# XPDR_Board_2.net
KiCad netlist of a schematic drawn in EAGLE
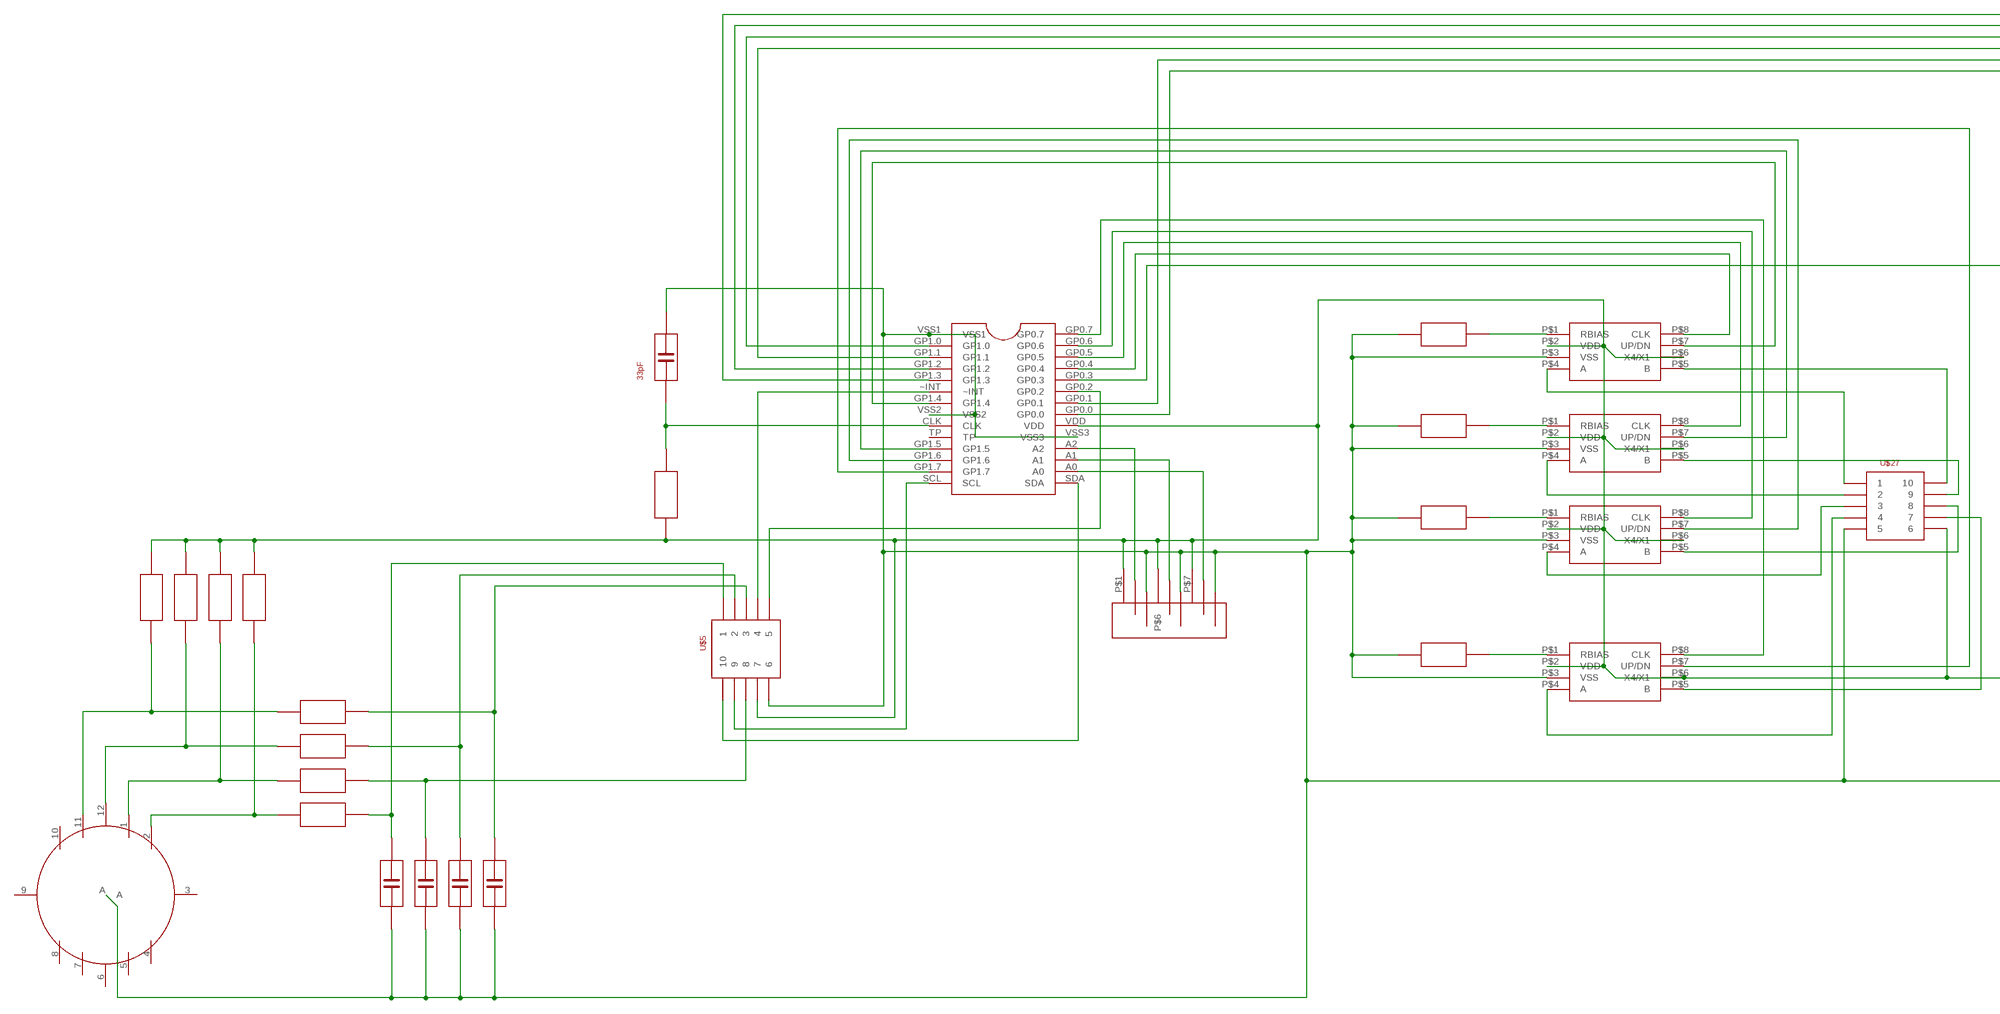
[diagram p0: schematic, sheet 1, part 1 of 2]
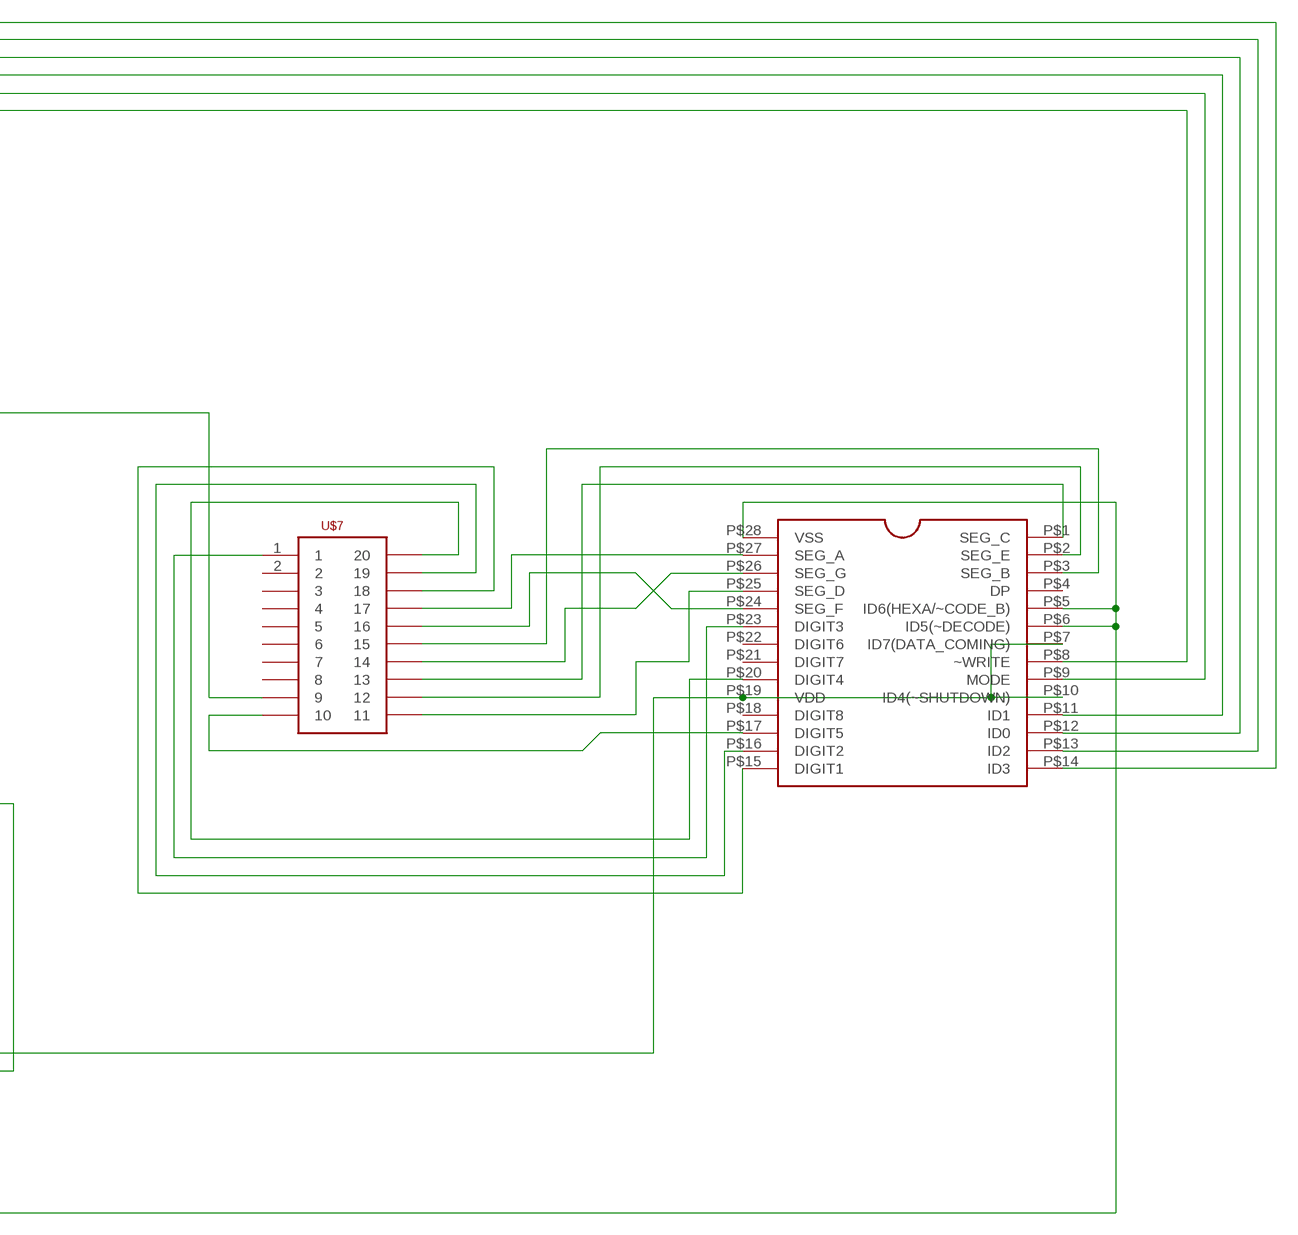
[diagram p1: schematic, sheet 1, part 2 of 2]

(export (version "E")
  (design (tool "Eeschema 10.0.6"))
  (components
    (comp (ref "U$1")
      (value "LS7084")
      (footprint "eagle-import:LS7084")
      (libsource (lib "eagle-import") (part "LS7084"))
    )
    (comp (ref "U$2")
      (value "LS7084")
      (footprint "eagle-import:LS7084")
      (libsource (lib "eagle-import") (part "LS7084"))
    )
    (comp (ref "U$3")
      (value "LS7084")
      (footprint "eagle-import:LS7084")
      (libsource (lib "eagle-import") (part "LS7084"))
    )
    (comp (ref "U$4")
      (value "LS7084")
      (footprint "eagle-import:LS7084")
      (libsource (lib "eagle-import") (part "LS7084"))
    )
    (comp (ref "U$5")
      (value "LISTA_2X5")
      (footprint "eagle-import:LISTA_2X5")
      (libsource (lib "eagle-import") (part "LISTA_2X5"))
    )
    (comp (ref "U$6")
      (value "ICM7228A")
      (footprint "eagle-import:ICM7228A")
      (libsource (lib "eagle-import") (part "ICM7228A"))
    )
    (comp (ref "U$7")
      (value "LISTA_2X10")
      (footprint "eagle-import:LISTA_2X10")
      (libsource (lib "eagle-import") (part "LISTA_2X10"))
    )
    (comp (ref "U$8")
      (value "470M")
      (footprint "eagle-import:REZISTOR")
      (libsource (lib "eagle-import") (part "REZISTOR"))
    )
    (comp (ref "U$9")
      (value "MCP23016")
      (footprint "eagle-import:MCP23016")
      (libsource (lib "eagle-import") (part "MCP23016"))
    )
    (comp (ref "U$10")
      (value "470M")
      (footprint "eagle-import:REZISTOR")
      (libsource (lib "eagle-import") (part "REZISTOR"))
    )
    (comp (ref "U$11")
      (value "ADRESA_0..2")
      (footprint "eagle-import:ADRESA_0..2")
      (libsource (lib "eagle-import") (part "ADRESA_0..2"))
    )
    (comp (ref "U$12")
      (value "470M")
      (footprint "eagle-import:REZISTOR")
      (libsource (lib "eagle-import") (part "REZISTOR"))
    )
    (comp (ref "U$13")
      (value "470M")
      (footprint "eagle-import:REZISTOR")
      (libsource (lib "eagle-import") (part "REZISTOR"))
    )
    (comp (ref "U$14")
      (value "3.9k")
      (footprint "eagle-import:REZISTOR")
      (libsource (lib "eagle-import") (part "REZISTOR"))
    )
    (comp (ref "U$15")
      (value "33pF")
      (footprint "eagle-import:KONDENZATOR")
      (libsource (lib "eagle-import") (part "KONDENZATOR"))
    )
    (comp (ref "U$16")
      (value "ROTARY_SWITCH")
      (footprint "eagle-import:ROTARY_SWITCH")
      (libsource (lib "eagle-import") (part "ROTARY_SWITCH"))
    )
    (comp (ref "U$17")
      (value "REZISTOR")
      (footprint "eagle-import:REZISTOR")
      (libsource (lib "eagle-import") (part "REZISTOR"))
    )
    (comp (ref "U$18")
      (value "REZISTOR")
      (footprint "eagle-import:REZISTOR")
      (libsource (lib "eagle-import") (part "REZISTOR"))
    )
    (comp (ref "U$19")
      (value "REZISTOR")
      (footprint "eagle-import:REZISTOR")
      (libsource (lib "eagle-import") (part "REZISTOR"))
    )
    (comp (ref "U$20")
      (value "REZISTOR")
      (footprint "eagle-import:REZISTOR")
      (libsource (lib "eagle-import") (part "REZISTOR"))
    )
    (comp (ref "U$21")
      (value "REZISTOR")
      (footprint "eagle-import:REZISTOR")
      (libsource (lib "eagle-import") (part "REZISTOR"))
    )
    (comp (ref "U$22")
      (value "REZISTOR")
      (footprint "eagle-import:REZISTOR")
      (libsource (lib "eagle-import") (part "REZISTOR"))
    )
    (comp (ref "U$23")
      (value "REZISTOR")
      (footprint "eagle-import:REZISTOR")
      (libsource (lib "eagle-import") (part "REZISTOR"))
    )
    (comp (ref "U$24")
      (value "REZISTOR")
      (footprint "eagle-import:REZISTOR")
      (libsource (lib "eagle-import") (part "REZISTOR"))
    )
    (comp (ref "U$25")
      (value "KONDENZATOR")
      (footprint "eagle-import:KONDENZATOR")
      (libsource (lib "eagle-import") (part "KONDENZATOR"))
    )
    (comp (ref "U$26")
      (value "KONDENZATOR")
      (footprint "eagle-import:KONDENZATOR")
      (libsource (lib "eagle-import") (part "KONDENZATOR"))
    )
    (comp (ref "U$27")
      (value "LISTA_2X5")
      (footprint "eagle-import:LISTA_2X5")
      (libsource (lib "eagle-import") (part "LISTA_2X5"))
    )
    (comp (ref "U$28")
      (value "KONDENZATOR")
      (footprint "eagle-import:KONDENZATOR")
      (libsource (lib "eagle-import") (part "KONDENZATOR"))
    )
    (comp (ref "U$29")
      (value "KONDENZATOR")
      (footprint "eagle-import:KONDENZATOR")
      (libsource (lib "eagle-import") (part "KONDENZATOR"))
    )
  )
  (nets
    (net (code "1") (name "Net-(U$1-A)") (class "Default")
      (node (ref "U$1") (pin "P$4") (pinfunction "A_P$4") (pintype "bidirectional"))
      (node (ref "U$27") (pin "1") (pinfunction "1_1") (pintype "bidirectional"))
    )
    (net (code "2") (name "Net-(U$1-B)") (class "Default")
      (node (ref "U$1") (pin "P$5") (pinfunction "B_P$5") (pintype "bidirectional"))
      (node (ref "U$27") (pin "10") (pinfunction "10_10") (pintype "bidirectional"))
    )
    (net (code "3") (name "Net-(U$1-CLK)") (class "Default")
      (node (ref "U$1") (pin "P$8") (pinfunction "CLK_P$8") (pintype "bidirectional"))
      (node (ref "U$9") (pin "GP0.4") (pinfunction "GP0.4_GP0.4") (pintype "bidirectional"))
    )
    (net (code "4") (name "Net-(U$1-RBIAS)") (class "Default")
      (node (ref "U$1") (pin "P$1") (pinfunction "RBIAS_P$1") (pintype "bidirectional"))
      (node (ref "U$8") (pin "P$2") (pinfunction "P$2_P$2") (pintype "bidirectional"))
    )
    (net (code "5") (name "Net-(U$1-UP{slash}DN)") (class "Default")
      (node (ref "U$1") (pin "P$7") (pinfunction "UP/DN_P$7") (pintype "bidirectional"))
      (node (ref "U$9") (pin "GP1.4") (pinfunction "GP1.4_GP1.4") (pintype "bidirectional"))
    )
    (net (code "6") (name "Net-(U$1-VDD)") (class "Default")
      (node (ref "U$1") (pin "P$2") (pinfunction "VDD_P$2") (pintype "bidirectional"))
      (node (ref "U$1") (pin "P$6") (pinfunction "X4/X1_P$6") (pintype "bidirectional"))
      (node (ref "U$11") (pin "P$1") (pinfunction "P$1_P$1") (pintype "bidirectional"))
      (node (ref "U$11") (pin "P$6") (pinfunction "P$6_P$6") (pintype "bidirectional"))
      (node (ref "U$11") (pin "P$7") (pinfunction "P$7_P$7") (pintype "bidirectional"))
      (node (ref "U$14") (pin "P$1") (pinfunction "P$1_P$1") (pintype "bidirectional"))
      (node (ref "U$17") (pin "P$1") (pinfunction "P$1_P$1") (pintype "bidirectional"))
      (node (ref "U$18") (pin "P$1") (pinfunction "P$1_P$1") (pintype "bidirectional"))
      (node (ref "U$19") (pin "P$1") (pinfunction "P$1_P$1") (pintype "bidirectional"))
      (node (ref "U$2") (pin "P$2") (pinfunction "VDD_P$2") (pintype "bidirectional"))
      (node (ref "U$2") (pin "P$6") (pinfunction "X4/X1_P$6") (pintype "bidirectional"))
      (node (ref "U$20") (pin "P$1") (pinfunction "P$1_P$1") (pintype "bidirectional"))
      (node (ref "U$27") (pin "6") (pinfunction "6_6") (pintype "bidirectional"))
      (node (ref "U$3") (pin "P$2") (pinfunction "VDD_P$2") (pintype "bidirectional"))
      (node (ref "U$3") (pin "P$6") (pinfunction "X4/X1_P$6") (pintype "bidirectional"))
      (node (ref "U$4") (pin "P$2") (pinfunction "VDD_P$2") (pintype "bidirectional"))
      (node (ref "U$4") (pin "P$6") (pinfunction "X4/X1_P$6") (pintype "bidirectional"))
      (node (ref "U$5") (pin "7") (pinfunction "7_7") (pintype "bidirectional"))
      (node (ref "U$6") (pin "P$10") (pinfunction "ID4(~{SHUTDOWN})_P$10") (pintype "bidirectional"))
      (node (ref "U$6") (pin "P$19") (pinfunction "VDD_P$19") (pintype "bidirectional"))
      (node (ref "U$6") (pin "P$7") (pinfunction "ID7(DATA_COMING)_P$7") (pintype "bidirectional"))
      (node (ref "U$9") (pin "VDD") (pinfunction "VDD_VDD") (pintype "bidirectional"))
    )
    (net (code "7") (name "Net-(U$1-VSS)") (class "Default")
      (node (ref "U$1") (pin "P$3") (pinfunction "VSS_P$3") (pintype "bidirectional"))
      (node (ref "U$10") (pin "P$1") (pinfunction "P$1_P$1") (pintype "bidirectional"))
      (node (ref "U$11") (pin "P$3") (pinfunction "P$3_P$3") (pintype "bidirectional"))
      (node (ref "U$11") (pin "P$4") (pinfunction "P$4_P$4") (pintype "bidirectional"))
      (node (ref "U$11") (pin "P$9") (pinfunction "P$9_P$9") (pintype "bidirectional"))
      (node (ref "U$12") (pin "P$1") (pinfunction "P$1_P$1") (pintype "bidirectional"))
      (node (ref "U$13") (pin "P$1") (pinfunction "P$1_P$1") (pintype "bidirectional"))
      (node (ref "U$15") (pin "P$2") (pinfunction "P$2_P$2") (pintype "bidirectional"))
      (node (ref "U$16") (pin "A") (pinfunction "A_A") (pintype "bidirectional"))
      (node (ref "U$2") (pin "P$3") (pinfunction "VSS_P$3") (pintype "bidirectional"))
      (node (ref "U$25") (pin "P$1") (pinfunction "P$1_P$1") (pintype "bidirectional"))
      (node (ref "U$26") (pin "P$1") (pinfunction "P$1_P$1") (pintype "bidirectional"))
      (node (ref "U$27") (pin "5") (pinfunction "5_5") (pintype "bidirectional"))
      (node (ref "U$28") (pin "P$1") (pinfunction "P$1_P$1") (pintype "bidirectional"))
      (node (ref "U$29") (pin "P$1") (pinfunction "P$1_P$1") (pintype "bidirectional"))
      (node (ref "U$3") (pin "P$3") (pinfunction "VSS_P$3") (pintype "bidirectional"))
      (node (ref "U$4") (pin "P$3") (pinfunction "VSS_P$3") (pintype "bidirectional"))
      (node (ref "U$5") (pin "6") (pinfunction "6_6") (pintype "bidirectional"))
      (node (ref "U$6") (pin "P$28") (pinfunction "VSS_P$28") (pintype "bidirectional"))
      (node (ref "U$6") (pin "P$5") (pinfunction "ID6(HEXA/~{CODE_B})_P$5") (pintype "bidirectional"))
      (node (ref "U$6") (pin "P$6") (pinfunction "ID5(~{DECODE})_P$6") (pintype "bidirectional"))
      (node (ref "U$8") (pin "P$1") (pinfunction "P$1_P$1") (pintype "bidirectional"))
      (node (ref "U$9") (pin "VSS1") (pinfunction "VSS1_VSS1") (pintype "bidirectional"))
      (node (ref "U$9") (pin "VSS2") (pinfunction "VSS2_VSS2") (pintype "bidirectional"))
      (node (ref "U$9") (pin "VSS3") (pinfunction "VSS3_VSS3") (pintype "bidirectional"))
    )
    (net (code "8") (name "Net-(U$2-A)") (class "Default")
      (node (ref "U$2") (pin "P$4") (pinfunction "A_P$4") (pintype "bidirectional"))
      (node (ref "U$27") (pin "2") (pinfunction "2_2") (pintype "bidirectional"))
    )
    (net (code "9") (name "Net-(U$2-B)") (class "Default")
      (node (ref "U$2") (pin "P$5") (pinfunction "B_P$5") (pintype "bidirectional"))
      (node (ref "U$27") (pin "9") (pinfunction "9_9") (pintype "bidirectional"))
    )
    (net (code "10") (name "Net-(U$2-CLK)") (class "Default")
      (node (ref "U$2") (pin "P$8") (pinfunction "CLK_P$8") (pintype "bidirectional"))
      (node (ref "U$9") (pin "GP0.5") (pinfunction "GP0.5_GP0.5") (pintype "bidirectional"))
    )
    (net (code "11") (name "Net-(U$2-RBIAS)") (class "Default")
      (node (ref "U$10") (pin "P$2") (pinfunction "P$2_P$2") (pintype "bidirectional"))
      (node (ref "U$2") (pin "P$1") (pinfunction "RBIAS_P$1") (pintype "bidirectional"))
    )
    (net (code "12") (name "Net-(U$2-UP{slash}DN)") (class "Default")
      (node (ref "U$2") (pin "P$7") (pinfunction "UP/DN_P$7") (pintype "bidirectional"))
      (node (ref "U$9") (pin "GP1.5") (pinfunction "GP1.5_GP1.5") (pintype "bidirectional"))
    )
    (net (code "13") (name "Net-(U$3-A)") (class "Default")
      (node (ref "U$27") (pin "3") (pinfunction "3_3") (pintype "bidirectional"))
      (node (ref "U$3") (pin "P$4") (pinfunction "A_P$4") (pintype "bidirectional"))
    )
    (net (code "14") (name "Net-(U$3-B)") (class "Default")
      (node (ref "U$27") (pin "8") (pinfunction "8_8") (pintype "bidirectional"))
      (node (ref "U$3") (pin "P$5") (pinfunction "B_P$5") (pintype "bidirectional"))
    )
    (net (code "15") (name "Net-(U$3-CLK)") (class "Default")
      (node (ref "U$3") (pin "P$8") (pinfunction "CLK_P$8") (pintype "bidirectional"))
      (node (ref "U$9") (pin "GP0.6") (pinfunction "GP0.6_GP0.6") (pintype "bidirectional"))
    )
    (net (code "16") (name "Net-(U$3-RBIAS)") (class "Default")
      (node (ref "U$12") (pin "P$2") (pinfunction "P$2_P$2") (pintype "bidirectional"))
      (node (ref "U$3") (pin "P$1") (pinfunction "RBIAS_P$1") (pintype "bidirectional"))
    )
    (net (code "17") (name "Net-(U$3-UP{slash}DN)") (class "Default")
      (node (ref "U$3") (pin "P$7") (pinfunction "UP/DN_P$7") (pintype "bidirectional"))
      (node (ref "U$9") (pin "GP1.6") (pinfunction "GP1.6_GP1.6") (pintype "bidirectional"))
    )
    (net (code "18") (name "Net-(U$4-A)") (class "Default")
      (node (ref "U$27") (pin "4") (pinfunction "4_4") (pintype "bidirectional"))
      (node (ref "U$4") (pin "P$4") (pinfunction "A_P$4") (pintype "bidirectional"))
    )
    (net (code "19") (name "Net-(U$4-B)") (class "Default")
      (node (ref "U$27") (pin "7") (pinfunction "7_7") (pintype "bidirectional"))
      (node (ref "U$4") (pin "P$5") (pinfunction "B_P$5") (pintype "bidirectional"))
    )
    (net (code "20") (name "Net-(U$4-CLK)") (class "Default")
      (node (ref "U$4") (pin "P$8") (pinfunction "CLK_P$8") (pintype "bidirectional"))
      (node (ref "U$9") (pin "GP0.7") (pinfunction "GP0.7_GP0.7") (pintype "bidirectional"))
    )
    (net (code "21") (name "Net-(U$4-RBIAS)") (class "Default")
      (node (ref "U$13") (pin "P$2") (pinfunction "P$2_P$2") (pintype "bidirectional"))
      (node (ref "U$4") (pin "P$1") (pinfunction "RBIAS_P$1") (pintype "bidirectional"))
    )
    (net (code "22") (name "Net-(U$4-UP{slash}DN)") (class "Default")
      (node (ref "U$4") (pin "P$7") (pinfunction "UP/DN_P$7") (pintype "bidirectional"))
      (node (ref "U$9") (pin "GP1.7") (pinfunction "GP1.7_GP1.7") (pintype "bidirectional"))
    )
    (net (code "23") (name "Net-(U$5-Pad5)") (class "Default")
      (node (ref "U$5") (pin "5") (pinfunction "5_5") (pintype "bidirectional"))
      (node (ref "U$9") (pin "GP0.2") (pinfunction "GP0.2_GP0.2") (pintype "bidirectional"))
    )
    (net (code "24") (name "Net-(U$5-Pad9)") (class "Default")
      (node (ref "U$5") (pin "9") (pinfunction "9_9") (pintype "bidirectional"))
      (node (ref "U$9") (pin "SCL") (pinfunction "SCL_SCL") (pintype "bidirectional"))
    )
    (net (code "25") (name "Net-(U$5-Pad10)") (class "Default")
      (node (ref "U$5") (pin "10") (pinfunction "10_10") (pintype "bidirectional"))
      (node (ref "U$9") (pin "SDA") (pinfunction "SDA_SDA") (pintype "bidirectional"))
    )
    (net (code "26") (name "Net-(U$6-DIGIT1)") (class "Default")
      (node (ref "U$6") (pin "P$15") (pinfunction "DIGIT1_P$15") (pintype "bidirectional"))
      (node (ref "U$7") (pin "18") (pinfunction "18_18") (pintype "bidirectional"))
    )
    (net (code "27") (name "Net-(U$6-DIGIT2)") (class "Default")
      (node (ref "U$6") (pin "P$16") (pinfunction "DIGIT2_P$16") (pintype "bidirectional"))
      (node (ref "U$7") (pin "19") (pinfunction "19_19") (pintype "bidirectional"))
    )
    (net (code "28") (name "Net-(U$6-DIGIT3)") (class "Default")
      (node (ref "U$6") (pin "P$23") (pinfunction "DIGIT3_P$23") (pintype "bidirectional"))
      (node (ref "U$7") (pin "1") (pinfunction "1_1") (pintype "bidirectional"))
    )
    (net (code "29") (name "Net-(U$6-DIGIT4)") (class "Default")
      (node (ref "U$6") (pin "P$20") (pinfunction "DIGIT4_P$20") (pintype "bidirectional"))
      (node (ref "U$7") (pin "20") (pinfunction "20_20") (pintype "bidirectional"))
    )
    (net (code "30") (name "Net-(U$6-DIGIT5)") (class "Default")
      (node (ref "U$6") (pin "P$17") (pinfunction "DIGIT5_P$17") (pintype "bidirectional"))
      (node (ref "U$7") (pin "10") (pinfunction "10_10") (pintype "bidirectional"))
    )
    (net (code "31") (name "Net-(U$6-ID0)") (class "Default")
      (node (ref "U$6") (pin "P$12") (pinfunction "ID0_P$12") (pintype "bidirectional"))
      (node (ref "U$9") (pin "GP1.0") (pinfunction "GP1.0_GP1.0") (pintype "bidirectional"))
    )
    (net (code "32") (name "Net-(U$6-ID1)") (class "Default")
      (node (ref "U$6") (pin "P$11") (pinfunction "ID1_P$11") (pintype "bidirectional"))
      (node (ref "U$9") (pin "GP1.1") (pinfunction "GP1.1_GP1.1") (pintype "bidirectional"))
    )
    (net (code "33") (name "Net-(U$6-ID2)") (class "Default")
      (node (ref "U$6") (pin "P$13") (pinfunction "ID2_P$13") (pintype "bidirectional"))
      (node (ref "U$9") (pin "GP1.2") (pinfunction "GP1.2_GP1.2") (pintype "bidirectional"))
    )
    (net (code "34") (name "Net-(U$6-ID3)") (class "Default")
      (node (ref "U$6") (pin "P$14") (pinfunction "ID3_P$14") (pintype "bidirectional"))
      (node (ref "U$9") (pin "GP1.3") (pinfunction "GP1.3_GP1.3") (pintype "bidirectional"))
    )
    (net (code "35") (name "Net-(U$6-MODE)") (class "Default")
      (node (ref "U$6") (pin "P$9") (pinfunction "MODE_P$9") (pintype "bidirectional"))
      (node (ref "U$9") (pin "GP0.1") (pinfunction "GP0.1_GP0.1") (pintype "bidirectional"))
    )
    (net (code "36") (name "Net-(U$6-SEG_A)") (class "Default")
      (node (ref "U$6") (pin "P$27") (pinfunction "SEG_A_P$27") (pintype "bidirectional"))
      (node (ref "U$7") (pin "17") (pinfunction "17_17") (pintype "bidirectional"))
    )
    (net (code "37") (name "Net-(U$6-SEG_B)") (class "Default")
      (node (ref "U$6") (pin "P$3") (pinfunction "SEG_B_P$3") (pintype "bidirectional"))
      (node (ref "U$7") (pin "15") (pinfunction "15_15") (pintype "bidirectional"))
    )
    (net (code "38") (name "Net-(U$6-SEG_C)") (class "Default")
      (node (ref "U$6") (pin "P$1") (pinfunction "SEG_C_P$1") (pintype "bidirectional"))
      (node (ref "U$7") (pin "13") (pinfunction "13_13") (pintype "bidirectional"))
    )
    (net (code "39") (name "Net-(U$6-SEG_D)") (class "Default")
      (node (ref "U$6") (pin "P$25") (pinfunction "SEG_D_P$25") (pintype "bidirectional"))
      (node (ref "U$7") (pin "11") (pinfunction "11_11") (pintype "bidirectional"))
    )
    (net (code "40") (name "Net-(U$6-SEG_E)") (class "Default")
      (node (ref "U$6") (pin "P$2") (pinfunction "SEG_E_P$2") (pintype "bidirectional"))
      (node (ref "U$7") (pin "12") (pinfunction "12_12") (pintype "bidirectional"))
    )
    (net (code "41") (name "Net-(U$6-SEG_F)") (class "Default")
      (node (ref "U$6") (pin "P$24") (pinfunction "SEG_F_P$24") (pintype "bidirectional"))
      (node (ref "U$7") (pin "16") (pinfunction "16_16") (pintype "bidirectional"))
    )
    (net (code "42") (name "Net-(U$6-SEG_G)") (class "Default")
      (node (ref "U$6") (pin "P$26") (pinfunction "SEG_G_P$26") (pintype "bidirectional"))
      (node (ref "U$7") (pin "14") (pinfunction "14_14") (pintype "bidirectional"))
    )
    (net (code "43") (name "Net-(U$6-~{WRITE})") (class "Default")
      (node (ref "U$6") (pin "P$8") (pinfunction "~{WRITE}_P$8") (pintype "bidirectional"))
      (node (ref "U$9") (pin "GP0.0") (pinfunction "GP0.0_GP0.0") (pintype "bidirectional"))
    )
    (net (code "44") (name "Net-(U$7-Pad9)") (class "Default")
      (node (ref "U$7") (pin "9") (pinfunction "9_9") (pintype "bidirectional"))
      (node (ref "U$9") (pin "GP0.3") (pinfunction "GP0.3_GP0.3") (pintype "bidirectional"))
    )
    (net (code "45") (name "Net-(U$9-~{INT})") (class "Default")
      (node (ref "U$5") (pin "4") (pinfunction "4_4") (pintype "bidirectional"))
      (node (ref "U$9") (pin "~INT") (pinfunction "~{INT}_~INT") (pintype "bidirectional"))
    )
    (net (code "46") (name "Net-(U$11-PadP$2)") (class "Default")
      (node (ref "U$11") (pin "P$2") (pinfunction "P$2_P$2") (pintype "bidirectional"))
      (node (ref "U$9") (pin "A2") (pinfunction "A2_A2") (pintype "bidirectional"))
    )
    (net (code "47") (name "Net-(U$11-PadP$5)") (class "Default")
      (node (ref "U$11") (pin "P$5") (pinfunction "P$5_P$5") (pintype "bidirectional"))
      (node (ref "U$9") (pin "A1") (pinfunction "A1_A1") (pintype "bidirectional"))
    )
    (net (code "48") (name "Net-(U$11-PadP$8)") (class "Default")
      (node (ref "U$11") (pin "P$8") (pinfunction "P$8_P$8") (pintype "bidirectional"))
      (node (ref "U$9") (pin "A0") (pinfunction "A0_A0") (pintype "bidirectional"))
    )
    (net (code "49") (name "Net-(U$14-PadP$2)") (class "Default")
      (node (ref "U$14") (pin "P$2") (pinfunction "P$2_P$2") (pintype "bidirectional"))
      (node (ref "U$15") (pin "P$1") (pinfunction "P$1_P$1") (pintype "bidirectional"))
      (node (ref "U$9") (pin "CLK") (pinfunction "CLK_CLK") (pintype "bidirectional"))
    )
    (net (code "50") (name "Net-(U$16-Pad1)") (class "Default")
      (node (ref "U$16") (pin "1") (pinfunction "1_1") (pintype "bidirectional"))
      (node (ref "U$19") (pin "P$2") (pinfunction "P$2_P$2") (pintype "bidirectional"))
      (node (ref "U$23") (pin "P$2") (pinfunction "P$2_P$2") (pintype "bidirectional"))
    )
    (net (code "51") (name "Net-(U$16-Pad2)") (class "Default")
      (node (ref "U$16") (pin "2") (pinfunction "2_2") (pintype "bidirectional"))
      (node (ref "U$20") (pin "P$2") (pinfunction "P$2_P$2") (pintype "bidirectional"))
      (node (ref "U$24") (pin "P$2") (pinfunction "P$2_P$2") (pintype "bidirectional"))
    )
    (net (code "52") (name "Net-(U$16-Pad11)") (class "Default")
      (node (ref "U$16") (pin "11") (pinfunction "11_11") (pintype "bidirectional"))
      (node (ref "U$17") (pin "P$2") (pinfunction "P$2_P$2") (pintype "bidirectional"))
      (node (ref "U$21") (pin "P$2") (pinfunction "P$2_P$2") (pintype "bidirectional"))
    )
    (net (code "53") (name "Net-(U$16-Pad12)") (class "Default")
      (node (ref "U$16") (pin "12") (pinfunction "12_12") (pintype "bidirectional"))
      (node (ref "U$18") (pin "P$2") (pinfunction "P$2_P$2") (pintype "bidirectional"))
      (node (ref "U$22") (pin "P$2") (pinfunction "P$2_P$2") (pintype "bidirectional"))
    )
    (net (code "54") (name "Net-(U$21-PadP$1)") (class "Default")
      (node (ref "U$21") (pin "P$1") (pinfunction "P$1_P$1") (pintype "bidirectional"))
      (node (ref "U$29") (pin "P$2") (pinfunction "P$2_P$2") (pintype "bidirectional"))
      (node (ref "U$5") (pin "3") (pinfunction "3_3") (pintype "bidirectional"))
    )
    (net (code "55") (name "Net-(U$22-PadP$1)") (class "Default")
      (node (ref "U$22") (pin "P$1") (pinfunction "P$1_P$1") (pintype "bidirectional"))
      (node (ref "U$28") (pin "P$2") (pinfunction "P$2_P$2") (pintype "bidirectional"))
      (node (ref "U$5") (pin "2") (pinfunction "2_2") (pintype "bidirectional"))
    )
    (net (code "56") (name "Net-(U$23-PadP$1)") (class "Default")
      (node (ref "U$23") (pin "P$1") (pinfunction "P$1_P$1") (pintype "bidirectional"))
      (node (ref "U$26") (pin "P$2") (pinfunction "P$2_P$2") (pintype "bidirectional"))
      (node (ref "U$5") (pin "8") (pinfunction "8_8") (pintype "bidirectional"))
    )
    (net (code "57") (name "Net-(U$24-PadP$1)") (class "Default")
      (node (ref "U$24") (pin "P$1") (pinfunction "P$1_P$1") (pintype "bidirectional"))
      (node (ref "U$25") (pin "P$2") (pinfunction "P$2_P$2") (pintype "bidirectional"))
      (node (ref "U$5") (pin "1") (pinfunction "1_1") (pintype "bidirectional"))
    )
    (net (code "58") (name "unconnected-(U$6-DIGIT6-PadP$22)") (class "Default")
      (node (ref "U$6") (pin "P$22") (pinfunction "DIGIT6_P$22") (pintype "bidirectional"))
    )
    (net (code "59") (name "unconnected-(U$6-DIGIT7-PadP$21)") (class "Default")
      (node (ref "U$6") (pin "P$21") (pinfunction "DIGIT7_P$21") (pintype "bidirectional"))
    )
    (net (code "60") (name "unconnected-(U$6-DIGIT8-PadP$18)") (class "Default")
      (node (ref "U$6") (pin "P$18") (pinfunction "DIGIT8_P$18") (pintype "bidirectional"))
    )
    (net (code "61") (name "unconnected-(U$6-DP-PadP$4)") (class "Default")
      (node (ref "U$6") (pin "P$4") (pinfunction "DP_P$4") (pintype "bidirectional"))
    )
    (net (code "62") (name "unconnected-(U$7-Pad2)") (class "Default")
      (node (ref "U$7") (pin "2") (pinfunction "2_2") (pintype "bidirectional"))
    )
    (net (code "63") (name "unconnected-(U$7-Pad3)") (class "Default")
      (node (ref "U$7") (pin "3") (pinfunction "3_3") (pintype "bidirectional"))
    )
    (net (code "64") (name "unconnected-(U$7-Pad4)") (class "Default")
      (node (ref "U$7") (pin "4") (pinfunction "4_4") (pintype "bidirectional"))
    )
    (net (code "65") (name "unconnected-(U$7-Pad5)") (class "Default")
      (node (ref "U$7") (pin "5") (pinfunction "5_5") (pintype "bidirectional"))
    )
    (net (code "66") (name "unconnected-(U$7-Pad6)") (class "Default")
      (node (ref "U$7") (pin "6") (pinfunction "6_6") (pintype "bidirectional"))
    )
    (net (code "67") (name "unconnected-(U$7-Pad7)") (class "Default")
      (node (ref "U$7") (pin "7") (pinfunction "7_7") (pintype "bidirectional"))
    )
    (net (code "68") (name "unconnected-(U$7-Pad8)") (class "Default")
      (node (ref "U$7") (pin "8") (pinfunction "8_8") (pintype "bidirectional"))
    )
    (net (code "69") (name "unconnected-(U$9-PadTP)") (class "Default")
      (node (ref "U$9") (pin "TP") (pinfunction "TP_TP") (pintype "bidirectional"))
    )
    (net (code "70") (name "unconnected-(U$16-Pad3)") (class "Default")
      (node (ref "U$16") (pin "3") (pinfunction "3_3") (pintype "bidirectional"))
    )
    (net (code "71") (name "unconnected-(U$16-Pad4)") (class "Default")
      (node (ref "U$16") (pin "4") (pinfunction "4_4") (pintype "bidirectional"))
    )
    (net (code "72") (name "unconnected-(U$16-Pad5)") (class "Default")
      (node (ref "U$16") (pin "5") (pinfunction "5_5") (pintype "bidirectional"))
    )
    (net (code "73") (name "unconnected-(U$16-Pad6)") (class "Default")
      (node (ref "U$16") (pin "6") (pinfunction "6_6") (pintype "bidirectional"))
    )
    (net (code "74") (name "unconnected-(U$16-Pad7)") (class "Default")
      (node (ref "U$16") (pin "7") (pinfunction "7_7") (pintype "bidirectional"))
    )
    (net (code "75") (name "unconnected-(U$16-Pad8)") (class "Default")
      (node (ref "U$16") (pin "8") (pinfunction "8_8") (pintype "bidirectional"))
    )
    (net (code "76") (name "unconnected-(U$16-Pad9)") (class "Default")
      (node (ref "U$16") (pin "9") (pinfunction "9_9") (pintype "bidirectional"))
    )
    (net (code "77") (name "unconnected-(U$16-Pad10)") (class "Default")
      (node (ref "U$16") (pin "10") (pinfunction "10_10") (pintype "bidirectional"))
    )
  )
)
